# Ch3and4.net
KiCad netlist of a schematic drawn in Altium Designer
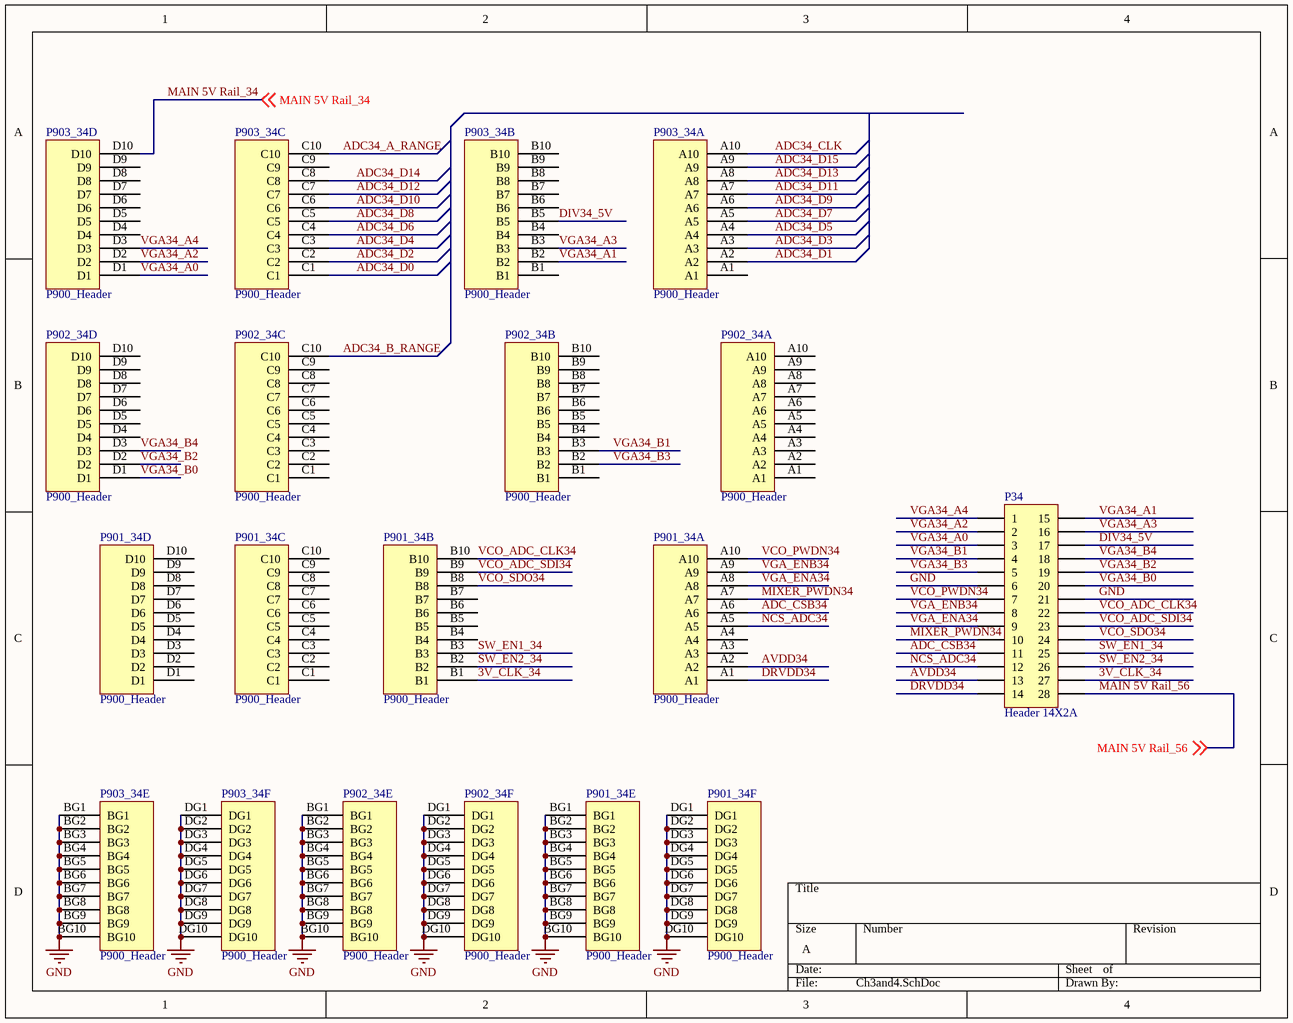
[diagram p0: Ch3and4.SchDoc]

(export (version "E")
  (design (tool "Eeschema 10.0.6"))
  (components
    (comp (ref "P34")
      (value "Header 14X2A")
      (footprint "HDR2X14_CEN")
      (description "Header, 14-Pin, Dual row")
      (fields (field (name "PUBLISHER") "Altium Limited"))
      (libsource (lib "Miscellaneous Connectors") (part "Header 14X2A"))
    )
    (comp (ref "P901_34")
      (value "P900_Header")
      (footprint "P900_header")
      (libsource (lib "MQP_lib") (part "P900_Header"))
    )
    (comp (ref "P902_34")
      (value "P900_Header")
      (footprint "P900_header")
      (libsource (lib "") (part "P900_Header_1"))
    )
    (comp (ref "P903_34")
      (value "P900_Header")
      (footprint "P900_header")
      (libsource (lib "") (part "P900_Header_1"))
    )
  )
  (nets
    (net (code "1") (name "/3V_CLK_34") (class "Default")
      (node (ref "P34") (pin "27") (pinfunction "27_27") (pintype "passive"))
      (node (ref "P901_34") (pin "B1") (pinfunction "B1_B1") (pintype "passive"))
    )
    (net (code "2") (name "/ADC34_A_RANGE") (class "Default")
      (node (ref "P903_34") (pin "C10") (pinfunction "C10_C10") (pintype "passive"))
    )
    (net (code "3") (name "/ADC34_B_RANGE") (class "Default")
      (node (ref "P902_34") (pin "C10") (pinfunction "C10_C10") (pintype "passive"))
    )
    (net (code "4") (name "/ADC34_CLK") (class "Default")
      (node (ref "P903_34") (pin "A10") (pinfunction "A10_A10") (pintype "passive"))
    )
    (net (code "5") (name "/ADC34_D0") (class "Default")
      (node (ref "P903_34") (pin "C1") (pinfunction "C1_C1") (pintype "passive"))
    )
    (net (code "6") (name "/ADC34_D1") (class "Default")
      (node (ref "P903_34") (pin "A2") (pinfunction "A2_A2") (pintype "passive"))
    )
    (net (code "7") (name "/ADC34_D2") (class "Default")
      (node (ref "P903_34") (pin "C2") (pinfunction "C2_C2") (pintype "passive"))
    )
    (net (code "8") (name "/ADC34_D3") (class "Default")
      (node (ref "P903_34") (pin "A3") (pinfunction "A3_A3") (pintype "passive"))
    )
    (net (code "9") (name "/ADC34_D4") (class "Default")
      (node (ref "P903_34") (pin "C3") (pinfunction "C3_C3") (pintype "passive"))
    )
    (net (code "10") (name "/ADC34_D5") (class "Default")
      (node (ref "P903_34") (pin "A4") (pinfunction "A4_A4") (pintype "passive"))
    )
    (net (code "11") (name "/ADC34_D6") (class "Default")
      (node (ref "P903_34") (pin "C4") (pinfunction "C4_C4") (pintype "passive"))
    )
    (net (code "12") (name "/ADC34_D7") (class "Default")
      (node (ref "P903_34") (pin "A5") (pinfunction "A5_A5") (pintype "passive"))
    )
    (net (code "13") (name "/ADC34_D8") (class "Default")
      (node (ref "P903_34") (pin "C5") (pinfunction "C5_C5") (pintype "passive"))
    )
    (net (code "14") (name "/ADC34_D9") (class "Default")
      (node (ref "P903_34") (pin "A6") (pinfunction "A6_A6") (pintype "passive"))
    )
    (net (code "15") (name "/ADC34_D10") (class "Default")
      (node (ref "P903_34") (pin "C6") (pinfunction "C6_C6") (pintype "passive"))
    )
    (net (code "16") (name "/ADC34_D11") (class "Default")
      (node (ref "P903_34") (pin "A7") (pinfunction "A7_A7") (pintype "passive"))
    )
    (net (code "17") (name "/ADC34_D12") (class "Default")
      (node (ref "P903_34") (pin "C7") (pinfunction "C7_C7") (pintype "passive"))
    )
    (net (code "18") (name "/ADC34_D13") (class "Default")
      (node (ref "P903_34") (pin "A8") (pinfunction "A8_A8") (pintype "passive"))
    )
    (net (code "19") (name "/ADC34_D14") (class "Default")
      (node (ref "P903_34") (pin "C8") (pinfunction "C8_C8") (pintype "passive"))
    )
    (net (code "20") (name "/ADC34_D15") (class "Default")
      (node (ref "P903_34") (pin "A9") (pinfunction "A9_A9") (pintype "passive"))
    )
    (net (code "21") (name "/ADC_CSB34") (class "Default")
      (node (ref "P34") (pin "11") (pinfunction "11_11") (pintype "passive"))
      (node (ref "P901_34") (pin "A6") (pinfunction "A6_A6") (pintype "passive"))
    )
    (net (code "22") (name "/AVDD34") (class "Default")
      (node (ref "P34") (pin "13") (pinfunction "13_13") (pintype "passive"))
      (node (ref "P901_34") (pin "A2") (pinfunction "A2_A2") (pintype "passive"))
    )
    (net (code "23") (name "/DIV34_5V") (class "Default")
      (node (ref "P34") (pin "17") (pinfunction "17_17") (pintype "passive"))
      (node (ref "P903_34") (pin "B5") (pinfunction "B5_B5") (pintype "passive"))
    )
    (net (code "24") (name "/DRVDD34") (class "Default")
      (node (ref "P34") (pin "14") (pinfunction "14_14") (pintype "passive"))
      (node (ref "P901_34") (pin "A1") (pinfunction "A1_A1") (pintype "passive"))
    )
    (net (code "25") (name "/MIXER_PWDN34") (class "Default")
      (node (ref "P34") (pin "10") (pinfunction "10_10") (pintype "passive"))
      (node (ref "P901_34") (pin "A7") (pinfunction "A7_A7") (pintype "passive"))
    )
    (net (code "26") (name "/NCS_ADC34") (class "Default")
      (node (ref "P34") (pin "12") (pinfunction "12_12") (pintype "passive"))
      (node (ref "P901_34") (pin "A5") (pinfunction "A5_A5") (pintype "passive"))
    )
    (net (code "27") (name "/SW_EN1_34") (class "Default")
      (node (ref "P34") (pin "25") (pinfunction "25_25") (pintype "passive"))
      (node (ref "P901_34") (pin "B3") (pinfunction "B3_B3") (pintype "passive"))
    )
    (net (code "28") (name "/SW_EN2_34") (class "Default")
      (node (ref "P34") (pin "26") (pinfunction "26_26") (pintype "passive"))
      (node (ref "P901_34") (pin "B2") (pinfunction "B2_B2") (pintype "passive"))
    )
    (net (code "29") (name "/VCO_ADC_CLK34") (class "Default")
      (node (ref "P34") (pin "22") (pinfunction "22_22") (pintype "passive"))
      (node (ref "P901_34") (pin "B10") (pinfunction "B10_B10") (pintype "passive"))
    )
    (net (code "30") (name "/VCO_ADC_SDI34") (class "Default")
      (node (ref "P34") (pin "23") (pinfunction "23_23") (pintype "passive"))
      (node (ref "P901_34") (pin "B9") (pinfunction "B9_B9") (pintype "passive"))
    )
    (net (code "31") (name "/VCO_PWDN34") (class "Default")
      (node (ref "P34") (pin "7") (pinfunction "7_7") (pintype "passive"))
      (node (ref "P901_34") (pin "A10") (pinfunction "A10_A10") (pintype "passive"))
    )
    (net (code "32") (name "/VCO_SDO34") (class "Default")
      (node (ref "P34") (pin "24") (pinfunction "24_24") (pintype "passive"))
      (node (ref "P901_34") (pin "B8") (pinfunction "B8_B8") (pintype "passive"))
    )
    (net (code "33") (name "/VGA34_A0") (class "Default")
      (node (ref "P34") (pin "3") (pinfunction "3_3") (pintype "passive"))
      (node (ref "P903_34") (pin "D1") (pinfunction "D1_D1") (pintype "passive"))
    )
    (net (code "34") (name "/VGA34_A1") (class "Default")
      (node (ref "P34") (pin "15") (pinfunction "15_15") (pintype "passive"))
      (node (ref "P903_34") (pin "B2") (pinfunction "B2_B2") (pintype "passive"))
    )
    (net (code "35") (name "/VGA34_A2") (class "Default")
      (node (ref "P34") (pin "2") (pinfunction "2_2") (pintype "passive"))
      (node (ref "P903_34") (pin "D2") (pinfunction "D2_D2") (pintype "passive"))
    )
    (net (code "36") (name "/VGA34_A3") (class "Default")
      (node (ref "P34") (pin "16") (pinfunction "16_16") (pintype "passive"))
      (node (ref "P903_34") (pin "B3") (pinfunction "B3_B3") (pintype "passive"))
    )
    (net (code "37") (name "/VGA34_A4") (class "Default")
      (node (ref "P34") (pin "1") (pinfunction "1_1") (pintype "passive"))
      (node (ref "P903_34") (pin "D3") (pinfunction "D3_D3") (pintype "passive"))
    )
    (net (code "38") (name "/VGA34_B0") (class "Default")
      (node (ref "P34") (pin "20") (pinfunction "20_20") (pintype "passive"))
      (node (ref "P902_34") (pin "D1") (pinfunction "D1_D1") (pintype "passive"))
    )
    (net (code "39") (name "/VGA34_B1") (class "Default")
      (node (ref "P34") (pin "4") (pinfunction "4_4") (pintype "passive"))
      (node (ref "P902_34") (pin "B3") (pinfunction "B3_B3") (pintype "passive"))
    )
    (net (code "40") (name "/VGA34_B2") (class "Default")
      (node (ref "P34") (pin "19") (pinfunction "19_19") (pintype "passive"))
      (node (ref "P902_34") (pin "D2") (pinfunction "D2_D2") (pintype "passive"))
    )
    (net (code "41") (name "/VGA34_B3") (class "Default")
      (node (ref "P34") (pin "5") (pinfunction "5_5") (pintype "passive"))
      (node (ref "P902_34") (pin "B2") (pinfunction "B2_B2") (pintype "passive"))
    )
    (net (code "42") (name "/VGA34_B4") (class "Default")
      (node (ref "P34") (pin "18") (pinfunction "18_18") (pintype "passive"))
      (node (ref "P902_34") (pin "D3") (pinfunction "D3_D3") (pintype "passive"))
    )
    (net (code "43") (name "/VGA_ENA34") (class "Default")
      (node (ref "P34") (pin "9") (pinfunction "9_9") (pintype "passive"))
      (node (ref "P901_34") (pin "A8") (pinfunction "A8_A8") (pintype "passive"))
    )
    (net (code "44") (name "/VGA_ENB34") (class "Default")
      (node (ref "P34") (pin "8") (pinfunction "8_8") (pintype "passive"))
      (node (ref "P901_34") (pin "A9") (pinfunction "A9_A9") (pintype "passive"))
    )
    (net (code "45") (name "GND") (class "Default")
      (node (ref "P34") (pin "21") (pinfunction "21_21") (pintype "passive"))
      (node (ref "P34") (pin "6") (pinfunction "6_6") (pintype "passive"))
      (node (ref "P901_34") (pin "BG1") (pinfunction "BG1_BG1") (pintype "passive"))
      (node (ref "P901_34") (pin "BG10") (pinfunction "BG10_BG10") (pintype "passive"))
      (node (ref "P901_34") (pin "BG2") (pinfunction "BG2_BG2") (pintype "passive"))
      (node (ref "P901_34") (pin "BG3") (pinfunction "BG3_BG3") (pintype "passive"))
      (node (ref "P901_34") (pin "BG4") (pinfunction "BG4_BG4") (pintype "passive"))
      (node (ref "P901_34") (pin "BG5") (pinfunction "BG5_BG5") (pintype "passive"))
      (node (ref "P901_34") (pin "BG6") (pinfunction "BG6_BG6") (pintype "passive"))
      (node (ref "P901_34") (pin "BG7") (pinfunction "BG7_BG7") (pintype "passive"))
      (node (ref "P901_34") (pin "BG8") (pinfunction "BG8_BG8") (pintype "passive"))
      (node (ref "P901_34") (pin "BG9") (pinfunction "BG9_BG9") (pintype "passive"))
      (node (ref "P901_34") (pin "DG1") (pinfunction "DG1_DG1") (pintype "passive"))
      (node (ref "P901_34") (pin "DG10") (pinfunction "DG10_DG10") (pintype "passive"))
      (node (ref "P901_34") (pin "DG2") (pinfunction "DG2_DG2") (pintype "passive"))
      (node (ref "P901_34") (pin "DG3") (pinfunction "DG3_DG3") (pintype "passive"))
      (node (ref "P901_34") (pin "DG4") (pinfunction "DG4_DG4") (pintype "passive"))
      (node (ref "P901_34") (pin "DG5") (pinfunction "DG5_DG5") (pintype "passive"))
      (node (ref "P901_34") (pin "DG6") (pinfunction "DG6_DG6") (pintype "passive"))
      (node (ref "P901_34") (pin "DG7") (pinfunction "DG7_DG7") (pintype "passive"))
      (node (ref "P901_34") (pin "DG8") (pinfunction "DG8_DG8") (pintype "passive"))
      (node (ref "P901_34") (pin "DG9") (pinfunction "DG9_DG9") (pintype "passive"))
      (node (ref "P902_34") (pin "BG1") (pinfunction "BG1_BG1") (pintype "passive"))
      (node (ref "P902_34") (pin "BG10") (pinfunction "BG10_BG10") (pintype "passive"))
      (node (ref "P902_34") (pin "BG2") (pinfunction "BG2_BG2") (pintype "passive"))
      (node (ref "P902_34") (pin "BG3") (pinfunction "BG3_BG3") (pintype "passive"))
      (node (ref "P902_34") (pin "BG4") (pinfunction "BG4_BG4") (pintype "passive"))
      (node (ref "P902_34") (pin "BG5") (pinfunction "BG5_BG5") (pintype "passive"))
      (node (ref "P902_34") (pin "BG6") (pinfunction "BG6_BG6") (pintype "passive"))
      (node (ref "P902_34") (pin "BG7") (pinfunction "BG7_BG7") (pintype "passive"))
      (node (ref "P902_34") (pin "BG8") (pinfunction "BG8_BG8") (pintype "passive"))
      (node (ref "P902_34") (pin "BG9") (pinfunction "BG9_BG9") (pintype "passive"))
      (node (ref "P902_34") (pin "DG1") (pinfunction "DG1_DG1") (pintype "passive"))
      (node (ref "P902_34") (pin "DG10") (pinfunction "DG10_DG10") (pintype "passive"))
      (node (ref "P902_34") (pin "DG2") (pinfunction "DG2_DG2") (pintype "passive"))
      (node (ref "P902_34") (pin "DG3") (pinfunction "DG3_DG3") (pintype "passive"))
      (node (ref "P902_34") (pin "DG4") (pinfunction "DG4_DG4") (pintype "passive"))
      (node (ref "P902_34") (pin "DG5") (pinfunction "DG5_DG5") (pintype "passive"))
      (node (ref "P902_34") (pin "DG6") (pinfunction "DG6_DG6") (pintype "passive"))
      (node (ref "P902_34") (pin "DG7") (pinfunction "DG7_DG7") (pintype "passive"))
      (node (ref "P902_34") (pin "DG8") (pinfunction "DG8_DG8") (pintype "passive"))
      (node (ref "P902_34") (pin "DG9") (pinfunction "DG9_DG9") (pintype "passive"))
      (node (ref "P903_34") (pin "BG1") (pinfunction "BG1_BG1") (pintype "passive"))
      (node (ref "P903_34") (pin "BG10") (pinfunction "BG10_BG10") (pintype "passive"))
      (node (ref "P903_34") (pin "BG2") (pinfunction "BG2_BG2") (pintype "passive"))
      (node (ref "P903_34") (pin "BG3") (pinfunction "BG3_BG3") (pintype "passive"))
      (node (ref "P903_34") (pin "BG4") (pinfunction "BG4_BG4") (pintype "passive"))
      (node (ref "P903_34") (pin "BG5") (pinfunction "BG5_BG5") (pintype "passive"))
      (node (ref "P903_34") (pin "BG6") (pinfunction "BG6_BG6") (pintype "passive"))
      (node (ref "P903_34") (pin "BG7") (pinfunction "BG7_BG7") (pintype "passive"))
      (node (ref "P903_34") (pin "BG8") (pinfunction "BG8_BG8") (pintype "passive"))
      (node (ref "P903_34") (pin "BG9") (pinfunction "BG9_BG9") (pintype "passive"))
      (node (ref "P903_34") (pin "DG1") (pinfunction "DG1_DG1") (pintype "passive"))
      (node (ref "P903_34") (pin "DG10") (pinfunction "DG10_DG10") (pintype "passive"))
      (node (ref "P903_34") (pin "DG2") (pinfunction "DG2_DG2") (pintype "passive"))
      (node (ref "P903_34") (pin "DG3") (pinfunction "DG3_DG3") (pintype "passive"))
      (node (ref "P903_34") (pin "DG4") (pinfunction "DG4_DG4") (pintype "passive"))
      (node (ref "P903_34") (pin "DG5") (pinfunction "DG5_DG5") (pintype "passive"))
      (node (ref "P903_34") (pin "DG6") (pinfunction "DG6_DG6") (pintype "passive"))
      (node (ref "P903_34") (pin "DG7") (pinfunction "DG7_DG7") (pintype "passive"))
      (node (ref "P903_34") (pin "DG8") (pinfunction "DG8_DG8") (pintype "passive"))
      (node (ref "P903_34") (pin "DG9") (pinfunction "DG9_DG9") (pintype "passive"))
    )
    (net (code "46") (name "MAIN 5V Rail_34") (class "Default")
      (node (ref "P903_34") (pin "D10") (pinfunction "D10_D10") (pintype "passive"))
    )
    (net (code "47") (name "MAIN 5V Rail_56") (class "Default")
      (node (ref "P34") (pin "28") (pinfunction "28_28") (pintype "passive"))
    )
    (net (code "48") (name "unconnected-(P901_34-PadA3)") (class "Default")
      (node (ref "P901_34") (pin "A3") (pinfunction "A3_A3") (pintype "passive"))
    )
    (net (code "49") (name "unconnected-(P901_34-PadA4)") (class "Default")
      (node (ref "P901_34") (pin "A4") (pinfunction "A4_A4") (pintype "passive"))
    )
    (net (code "50") (name "unconnected-(P901_34-PadB4)") (class "Default")
      (node (ref "P901_34") (pin "B4") (pinfunction "B4_B4") (pintype "passive"))
    )
    (net (code "51") (name "unconnected-(P901_34-PadB5)") (class "Default")
      (node (ref "P901_34") (pin "B5") (pinfunction "B5_B5") (pintype "passive"))
    )
    (net (code "52") (name "unconnected-(P901_34-PadB6)") (class "Default")
      (node (ref "P901_34") (pin "B6") (pinfunction "B6_B6") (pintype "passive"))
    )
    (net (code "53") (name "unconnected-(P901_34-PadB7)") (class "Default")
      (node (ref "P901_34") (pin "B7") (pinfunction "B7_B7") (pintype "passive"))
    )
    (net (code "54") (name "unconnected-(P901_34-PadC1)") (class "Default")
      (node (ref "P901_34") (pin "C1") (pinfunction "C1_C1") (pintype "passive"))
    )
    (net (code "55") (name "unconnected-(P901_34-PadC2)") (class "Default")
      (node (ref "P901_34") (pin "C2") (pinfunction "C2_C2") (pintype "passive"))
    )
    (net (code "56") (name "unconnected-(P901_34-PadC3)") (class "Default")
      (node (ref "P901_34") (pin "C3") (pinfunction "C3_C3") (pintype "passive"))
    )
    (net (code "57") (name "unconnected-(P901_34-PadC4)") (class "Default")
      (node (ref "P901_34") (pin "C4") (pinfunction "C4_C4") (pintype "passive"))
    )
    (net (code "58") (name "unconnected-(P901_34-PadC5)") (class "Default")
      (node (ref "P901_34") (pin "C5") (pinfunction "C5_C5") (pintype "passive"))
    )
    (net (code "59") (name "unconnected-(P901_34-PadC6)") (class "Default")
      (node (ref "P901_34") (pin "C6") (pinfunction "C6_C6") (pintype "passive"))
    )
    (net (code "60") (name "unconnected-(P901_34-PadC7)") (class "Default")
      (node (ref "P901_34") (pin "C7") (pinfunction "C7_C7") (pintype "passive"))
    )
    (net (code "61") (name "unconnected-(P901_34-PadC8)") (class "Default")
      (node (ref "P901_34") (pin "C8") (pinfunction "C8_C8") (pintype "passive"))
    )
    (net (code "62") (name "unconnected-(P901_34-PadC9)") (class "Default")
      (node (ref "P901_34") (pin "C9") (pinfunction "C9_C9") (pintype "passive"))
    )
    (net (code "63") (name "unconnected-(P901_34-PadC10)") (class "Default")
      (node (ref "P901_34") (pin "C10") (pinfunction "C10_C10") (pintype "passive"))
    )
    (net (code "64") (name "unconnected-(P901_34-PadD1)") (class "Default")
      (node (ref "P901_34") (pin "D1") (pinfunction "D1_D1") (pintype "passive"))
    )
    (net (code "65") (name "unconnected-(P901_34-PadD2)") (class "Default")
      (node (ref "P901_34") (pin "D2") (pinfunction "D2_D2") (pintype "passive"))
    )
    (net (code "66") (name "unconnected-(P901_34-PadD3)") (class "Default")
      (node (ref "P901_34") (pin "D3") (pinfunction "D3_D3") (pintype "passive"))
    )
    (net (code "67") (name "unconnected-(P901_34-PadD4)") (class "Default")
      (node (ref "P901_34") (pin "D4") (pinfunction "D4_D4") (pintype "passive"))
    )
    (net (code "68") (name "unconnected-(P901_34-PadD5)") (class "Default")
      (node (ref "P901_34") (pin "D5") (pinfunction "D5_D5") (pintype "passive"))
    )
    (net (code "69") (name "unconnected-(P901_34-PadD6)") (class "Default")
      (node (ref "P901_34") (pin "D6") (pinfunction "D6_D6") (pintype "passive"))
    )
    (net (code "70") (name "unconnected-(P901_34-PadD7)") (class "Default")
      (node (ref "P901_34") (pin "D7") (pinfunction "D7_D7") (pintype "passive"))
    )
    (net (code "71") (name "unconnected-(P901_34-PadD8)") (class "Default")
      (node (ref "P901_34") (pin "D8") (pinfunction "D8_D8") (pintype "passive"))
    )
    (net (code "72") (name "unconnected-(P901_34-PadD9)") (class "Default")
      (node (ref "P901_34") (pin "D9") (pinfunction "D9_D9") (pintype "passive"))
    )
    (net (code "73") (name "unconnected-(P901_34-PadD10)") (class "Default")
      (node (ref "P901_34") (pin "D10") (pinfunction "D10_D10") (pintype "passive"))
    )
    (net (code "74") (name "unconnected-(P902_34-PadA1)") (class "Default")
      (node (ref "P902_34") (pin "A1") (pinfunction "A1_A1") (pintype "passive"))
    )
    (net (code "75") (name "unconnected-(P902_34-PadA2)") (class "Default")
      (node (ref "P902_34") (pin "A2") (pinfunction "A2_A2") (pintype "passive"))
    )
    (net (code "76") (name "unconnected-(P902_34-PadA3)") (class "Default")
      (node (ref "P902_34") (pin "A3") (pinfunction "A3_A3") (pintype "passive"))
    )
    (net (code "77") (name "unconnected-(P902_34-PadA4)") (class "Default")
      (node (ref "P902_34") (pin "A4") (pinfunction "A4_A4") (pintype "passive"))
    )
    (net (code "78") (name "unconnected-(P902_34-PadA5)") (class "Default")
      (node (ref "P902_34") (pin "A5") (pinfunction "A5_A5") (pintype "passive"))
    )
    (net (code "79") (name "unconnected-(P902_34-PadA6)") (class "Default")
      (node (ref "P902_34") (pin "A6") (pinfunction "A6_A6") (pintype "passive"))
    )
    (net (code "80") (name "unconnected-(P902_34-PadA7)") (class "Default")
      (node (ref "P902_34") (pin "A7") (pinfunction "A7_A7") (pintype "passive"))
    )
    (net (code "81") (name "unconnected-(P902_34-PadA8)") (class "Default")
      (node (ref "P902_34") (pin "A8") (pinfunction "A8_A8") (pintype "passive"))
    )
    (net (code "82") (name "unconnected-(P902_34-PadA9)") (class "Default")
      (node (ref "P902_34") (pin "A9") (pinfunction "A9_A9") (pintype "passive"))
    )
    (net (code "83") (name "unconnected-(P902_34-PadA10)") (class "Default")
      (node (ref "P902_34") (pin "A10") (pinfunction "A10_A10") (pintype "passive"))
    )
    (net (code "84") (name "unconnected-(P902_34-PadB1)") (class "Default")
      (node (ref "P902_34") (pin "B1") (pinfunction "B1_B1") (pintype "passive"))
    )
    (net (code "85") (name "unconnected-(P902_34-PadB4)") (class "Default")
      (node (ref "P902_34") (pin "B4") (pinfunction "B4_B4") (pintype "passive"))
    )
    (net (code "86") (name "unconnected-(P902_34-PadB5)") (class "Default")
      (node (ref "P902_34") (pin "B5") (pinfunction "B5_B5") (pintype "passive"))
    )
    (net (code "87") (name "unconnected-(P902_34-PadB6)") (class "Default")
      (node (ref "P902_34") (pin "B6") (pinfunction "B6_B6") (pintype "passive"))
    )
    (net (code "88") (name "unconnected-(P902_34-PadB7)") (class "Default")
      (node (ref "P902_34") (pin "B7") (pinfunction "B7_B7") (pintype "passive"))
    )
    (net (code "89") (name "unconnected-(P902_34-PadB8)") (class "Default")
      (node (ref "P902_34") (pin "B8") (pinfunction "B8_B8") (pintype "passive"))
    )
    (net (code "90") (name "unconnected-(P902_34-PadB9)") (class "Default")
      (node (ref "P902_34") (pin "B9") (pinfunction "B9_B9") (pintype "passive"))
    )
    (net (code "91") (name "unconnected-(P902_34-PadB10)") (class "Default")
      (node (ref "P902_34") (pin "B10") (pinfunction "B10_B10") (pintype "passive"))
    )
    (net (code "92") (name "unconnected-(P902_34-PadC1)") (class "Default")
      (node (ref "P902_34") (pin "C1") (pinfunction "C1_C1") (pintype "passive"))
    )
    (net (code "93") (name "unconnected-(P902_34-PadC2)") (class "Default")
      (node (ref "P902_34") (pin "C2") (pinfunction "C2_C2") (pintype "passive"))
    )
    (net (code "94") (name "unconnected-(P902_34-PadC3)") (class "Default")
      (node (ref "P902_34") (pin "C3") (pinfunction "C3_C3") (pintype "passive"))
    )
    (net (code "95") (name "unconnected-(P902_34-PadC4)") (class "Default")
      (node (ref "P902_34") (pin "C4") (pinfunction "C4_C4") (pintype "passive"))
    )
    (net (code "96") (name "unconnected-(P902_34-PadC5)") (class "Default")
      (node (ref "P902_34") (pin "C5") (pinfunction "C5_C5") (pintype "passive"))
    )
    (net (code "97") (name "unconnected-(P902_34-PadC6)") (class "Default")
      (node (ref "P902_34") (pin "C6") (pinfunction "C6_C6") (pintype "passive"))
    )
    (net (code "98") (name "unconnected-(P902_34-PadC7)") (class "Default")
      (node (ref "P902_34") (pin "C7") (pinfunction "C7_C7") (pintype "passive"))
    )
    (net (code "99") (name "unconnected-(P902_34-PadC8)") (class "Default")
      (node (ref "P902_34") (pin "C8") (pinfunction "C8_C8") (pintype "passive"))
    )
    (net (code "100") (name "unconnected-(P902_34-PadC9)") (class "Default")
      (node (ref "P902_34") (pin "C9") (pinfunction "C9_C9") (pintype "passive"))
    )
    (net (code "101") (name "unconnected-(P902_34-PadD4)") (class "Default")
      (node (ref "P902_34") (pin "D4") (pinfunction "D4_D4") (pintype "passive"))
    )
    (net (code "102") (name "unconnected-(P902_34-PadD5)") (class "Default")
      (node (ref "P902_34") (pin "D5") (pinfunction "D5_D5") (pintype "passive"))
    )
    (net (code "103") (name "unconnected-(P902_34-PadD6)") (class "Default")
      (node (ref "P902_34") (pin "D6") (pinfunction "D6_D6") (pintype "passive"))
    )
    (net (code "104") (name "unconnected-(P902_34-PadD7)") (class "Default")
      (node (ref "P902_34") (pin "D7") (pinfunction "D7_D7") (pintype "passive"))
    )
    (net (code "105") (name "unconnected-(P902_34-PadD8)") (class "Default")
      (node (ref "P902_34") (pin "D8") (pinfunction "D8_D8") (pintype "passive"))
    )
    (net (code "106") (name "unconnected-(P902_34-PadD9)") (class "Default")
      (node (ref "P902_34") (pin "D9") (pinfunction "D9_D9") (pintype "passive"))
    )
    (net (code "107") (name "unconnected-(P902_34-PadD10)") (class "Default")
      (node (ref "P902_34") (pin "D10") (pinfunction "D10_D10") (pintype "passive"))
    )
    (net (code "108") (name "unconnected-(P903_34-PadA1)") (class "Default")
      (node (ref "P903_34") (pin "A1") (pinfunction "A1_A1") (pintype "passive"))
    )
    (net (code "109") (name "unconnected-(P903_34-PadB1)") (class "Default")
      (node (ref "P903_34") (pin "B1") (pinfunction "B1_B1") (pintype "passive"))
    )
    (net (code "110") (name "unconnected-(P903_34-PadB4)") (class "Default")
      (node (ref "P903_34") (pin "B4") (pinfunction "B4_B4") (pintype "passive"))
    )
    (net (code "111") (name "unconnected-(P903_34-PadB6)") (class "Default")
      (node (ref "P903_34") (pin "B6") (pinfunction "B6_B6") (pintype "passive"))
    )
    (net (code "112") (name "unconnected-(P903_34-PadB7)") (class "Default")
      (node (ref "P903_34") (pin "B7") (pinfunction "B7_B7") (pintype "passive"))
    )
    (net (code "113") (name "unconnected-(P903_34-PadB8)") (class "Default")
      (node (ref "P903_34") (pin "B8") (pinfunction "B8_B8") (pintype "passive"))
    )
    (net (code "114") (name "unconnected-(P903_34-PadB9)") (class "Default")
      (node (ref "P903_34") (pin "B9") (pinfunction "B9_B9") (pintype "passive"))
    )
    (net (code "115") (name "unconnected-(P903_34-PadB10)") (class "Default")
      (node (ref "P903_34") (pin "B10") (pinfunction "B10_B10") (pintype "passive"))
    )
    (net (code "116") (name "unconnected-(P903_34-PadC9)") (class "Default")
      (node (ref "P903_34") (pin "C9") (pinfunction "C9_C9") (pintype "passive"))
    )
    (net (code "117") (name "unconnected-(P903_34-PadD4)") (class "Default")
      (node (ref "P903_34") (pin "D4") (pinfunction "D4_D4") (pintype "passive"))
    )
    (net (code "118") (name "unconnected-(P903_34-PadD5)") (class "Default")
      (node (ref "P903_34") (pin "D5") (pinfunction "D5_D5") (pintype "passive"))
    )
    (net (code "119") (name "unconnected-(P903_34-PadD6)") (class "Default")
      (node (ref "P903_34") (pin "D6") (pinfunction "D6_D6") (pintype "passive"))
    )
    (net (code "120") (name "unconnected-(P903_34-PadD7)") (class "Default")
      (node (ref "P903_34") (pin "D7") (pinfunction "D7_D7") (pintype "passive"))
    )
    (net (code "121") (name "unconnected-(P903_34-PadD8)") (class "Default")
      (node (ref "P903_34") (pin "D8") (pinfunction "D8_D8") (pintype "passive"))
    )
    (net (code "122") (name "unconnected-(P903_34-PadD9)") (class "Default")
      (node (ref "P903_34") (pin "D9") (pinfunction "D9_D9") (pintype "passive"))
    )
  )
)
